# Microcontroller_Unit.net
KiCad netlist of a schematic drawn in Altium Designer
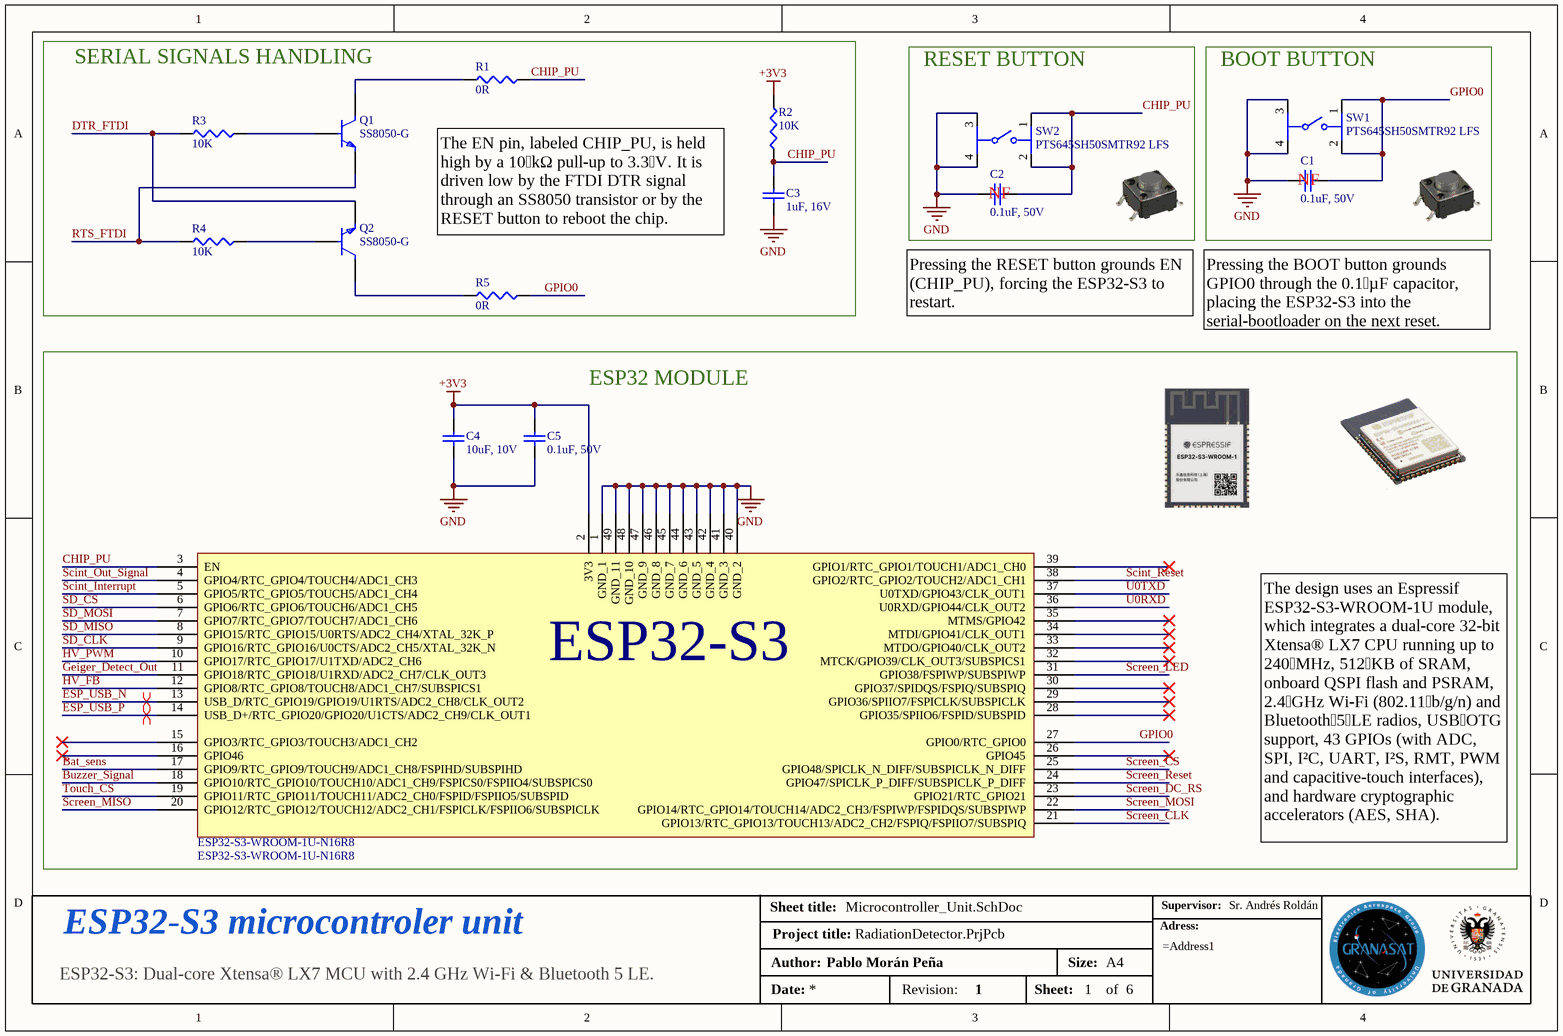
[diagram p0: Microcontroller_Unit.SchDoc]

(export (version "E")
  (design (tool "Eeschema 10.0.6"))
  (components
    (comp (ref "C1")
      (value "0.1uF, 50V")
      (footprint "CAP 0402_1005")
      (description "CAP CER 0.1UF 50V X7R 0402")
      (fields
        (field (name "MANUFACTURER") "Samsung")
        (field (name "MANUFACTURER PART NUMBER") "CL05B104KB5NNNC")
      )
      (libsource (lib "Schlib") (part "CL05B104KB5NNNC"))
    )
    (comp (ref "C2")
      (value "0.1uF, 50V")
      (footprint "CAP 0402_1005")
      (description "CAP CER 0.1UF 50V X7R 0402")
      (fields
        (field (name "MANUFACTURER") "Samsung")
        (field (name "MANUFACTURER PART NUMBER") "CL05B104KB5NNNC")
      )
      (libsource (lib "Schlib") (part "CL05B104KB5NNNC"))
    )
    (comp (ref "C3")
      (value "1uF, 16V")
      (footprint "CAP 0402_1005")
      (description "CAP CER 1UF 16V X5R 0402")
      (fields
        (field (name "MANUFACTURER") "Samsung Electro-Mechanics")
        (field (name "MANUFACTURER PART NUMBER") "CL05A105KO5NNNC")
      )
      (libsource (lib "Schlib") (part "CL05A105KO5NNNC"))
    )
    (comp (ref "C4")
      (value "10uF, 10V")
      (footprint "CAP 0402_1005")
      (description "CAP CER 10UF 10V X5R 0402")
      (fields
        (field (name "MANUFACTURER") "Samsung Electro-Mechanics")
        (field (name "MANUFACTURER PART NUMBER") "CL05A106MP8NUB8")
      )
      (libsource (lib "Schlib") (part "CL05A106MP8NUB8"))
    )
    (comp (ref "C5")
      (value "0.1uF, 50V")
      (footprint "CAP 0402_1005")
      (description "CAP CER 0.1UF 50V X7R 0402")
      (fields
        (field (name "MANUFACTURER") "Samsung")
        (field (name "MANUFACTURER PART NUMBER") "CL05B104KB5NNNC")
      )
      (libsource (lib "Schlib") (part "CL05B104KB5NNNC"))
    )
    (comp (ref "ESP32-S3-WROOM-1U-N16R8")
      (value "ESP32-S3-WROOM-1U-N16R8")
      (footprint "ESP32S3WROOM1N8R2")
      (description "SMD Module, ESP32-S3R8 With 8 mb")
      (fields (field (name "MANUFACTURER") "Espressif Systems") (field (name "LCSC PART NUMBER") "C2913202"))
      (libsource (lib "Schlib") (part "ESP32-S3-WROOM-1-N16R8"))
    )
    (comp (ref "Q1")
      (value "SS8050-G")
      (footprint "FP-SS8050-G-IPC_B")
      (description "Transistores - Bipolar (BJT) - Simple NPN 25 V 1.5 A 100MHz 300 mW Montaje en superficie SOT-23-3")
      (fields (field (name "MANUFACTURER") "Comchip") (field (name "LCSC PART NUMBER") "C164886"))
      (libsource (lib "Schlib") (part "SS8050-G"))
    )
    (comp (ref "Q2")
      (value "SS8050-G")
      (footprint "FP-SS8050-G-IPC_B")
      (description "Transistores - Bipolar (BJT) - Simple NPN 25 V 1.5 A 100MHz 300 mW Montaje en superficie SOT-23-3")
      (fields (field (name "MANUFACTURER") "Comchip") (field (name "LCSC PART NUMBER") "C164886"))
      (libsource (lib "Schlib") (part "SS8050-G"))
    )
    (comp (ref "R1")
      (value "0R")
      (footprint "RESC1005X37N")
      (description "RES 0 OHM JUMPER 1/16W 0402")
      (fields
        (field (name "MANUFACTURER") "Yageo")
        (field (name "MANUFACTURER PART NUMBER") "RC0402JR-070RL")
      )
      (libsource (lib "Schlib") (part "RC0402JR-070RL"))
    )
    (comp (ref "R2")
      (value "10K")
      (footprint "RESC1005X37N")
      (description "RES SMD 10K OHM 1% 1/16W 0402")
      (fields
        (field (name "MANUFACTURER") "Yageo")
        (field (name "MANUFACTURER PART NUMBER") "AC0402FR-0710KL")
      )
      (libsource (lib "Schlib") (part "AC0402FR-0710KL"))
    )
    (comp (ref "R3")
      (value "10K")
      (footprint "RESC1005X37N")
      (description "RES SMD 10K OHM 1% 1/16W 0402")
      (fields
        (field (name "MANUFACTURER") "Yageo")
        (field (name "MANUFACTURER PART NUMBER") "AC0402FR-0710KL")
      )
      (libsource (lib "Schlib") (part "AC0402FR-0710KL"))
    )
    (comp (ref "R4")
      (value "10K")
      (footprint "RESC1005X37N")
      (description "RES SMD 10K OHM 1% 1/16W 0402")
      (fields
        (field (name "MANUFACTURER") "Yageo")
        (field (name "MANUFACTURER PART NUMBER") "AC0402FR-0710KL")
      )
      (libsource (lib "Schlib") (part "AC0402FR-0710KL"))
    )
    (comp (ref "R5")
      (value "0R")
      (footprint "RESC1005X37N")
      (description "RES 0 OHM JUMPER 1/16W 0402")
      (fields
        (field (name "MANUFACTURER") "Yageo")
        (field (name "MANUFACTURER PART NUMBER") "RC0402JR-070RL")
      )
      (libsource (lib "Schlib") (part "RC0402JR-070RL"))
    )
    (comp (ref "SW1")
      (value "PTS645SH50SMTR92 LFS")
      (footprint "FP-PTS645SH50SMTR92LFS-MFG")
      (description "SWITCH TACTILE SPST-NO 0.05A 12V")
      (fields
        (field (name "MANUFACTURER") "ITT C&K")
        (field (name "MANUFACTURER PART NUMBER") "PTS645SH50SMTR92LFS")
      )
      (libsource (lib "Schlib") (part "PTS645SH50SMTR92LFS"))
    )
    (comp (ref "SW2")
      (value "PTS645SH50SMTR92 LFS")
      (footprint "FP-PTS645SH50SMTR92LFS-MFG")
      (description "SWITCH TACTILE SPST-NO 0.05A 12V")
      (fields
        (field (name "MANUFACTURER") "ITT C&K")
        (field (name "MANUFACTURER PART NUMBER") "PTS645SH50SMTR92LFS")
      )
      (libsource (lib "Schlib") (part "PTS645SH50SMTR92LFS"))
    )
  )
  (nets
    (net (code "1") (name "+3V3") (class "Default")
      (node (ref "C4") (pin "2") (pinfunction "2_2") (pintype "passive"))
      (node (ref "C5") (pin "2") (pinfunction "2_2") (pintype "passive"))
      (node (ref "ESP32-S3-WROOM-1U-N16R8") (pin "2") (pinfunction "3V3_2") (pintype "passive"))
      (node (ref "R2") (pin "2") (pinfunction "2_2") (pintype "passive"))
    )
    (net (code "2") (name "/Bat_sens") (class "Default")
      (node (ref "ESP32-S3-WROOM-1U-N16R8") (pin "17") (pinfunction "GPIO9/RTC_GPIO9/TOUCH9/ADC1_CH8/FSPIHD/SUBSPIHD_17") (pintype "passive"))
    )
    (net (code "3") (name "/Buzzer_Signal") (class "Default")
      (node (ref "ESP32-S3-WROOM-1U-N16R8") (pin "18") (pinfunction "GPIO10/RTC_GPIO10/TOUCH10/ADC1_CH9/FSPICS0/FSPIIO4/SUBSPICS0_18") (pintype "passive"))
    )
    (net (code "4") (name "/CHIP_PU") (class "Default")
      (node (ref "C2") (pin "2") (pinfunction "2_2") (pintype "passive"))
      (node (ref "C3") (pin "2") (pinfunction "2_2") (pintype "passive"))
      (node (ref "ESP32-S3-WROOM-1U-N16R8") (pin "3") (pinfunction "EN_3") (pintype "passive"))
      (node (ref "R1") (pin "2") (pinfunction "2_2") (pintype "passive"))
      (node (ref "R2") (pin "1") (pinfunction "1_1") (pintype "passive"))
      (node (ref "SW2") (pin "1") (pinfunction "1_1") (pintype "passive"))
      (node (ref "SW2") (pin "2") (pinfunction "2_2") (pintype "passive"))
    )
    (net (code "5") (name "/DTR_FTDI") (class "Default")
      (node (ref "Q2") (pin "2") (pinfunction "E_2") (pintype "passive"))
      (node (ref "R3") (pin "1") (pinfunction "1_1") (pintype "passive"))
    )
    (net (code "6") (name "/ESP_USB_N") (class "Default")
      (node (ref "ESP32-S3-WROOM-1U-N16R8") (pin "13") (pinfunction "USB_D/RTC_GPIO19/GPIO19/U1RTS/ADC2_CH8/CLK_OUT2_13") (pintype "passive"))
    )
    (net (code "7") (name "/ESP_USB_P") (class "Default")
      (node (ref "ESP32-S3-WROOM-1U-N16R8") (pin "14") (pinfunction "USB_D+/RTC_GPIO20/GPIO20/U1CTS/ADC2_CH9/CLK_OUT1_14") (pintype "passive"))
    )
    (net (code "8") (name "/GPIO0") (class "Default")
      (node (ref "C1") (pin "2") (pinfunction "2_2") (pintype "passive"))
      (node (ref "ESP32-S3-WROOM-1U-N16R8") (pin "27") (pinfunction "GPIO0/RTC_GPIO0_27") (pintype "passive"))
      (node (ref "R5") (pin "2") (pinfunction "2_2") (pintype "passive"))
      (node (ref "SW1") (pin "1") (pinfunction "1_1") (pintype "passive"))
      (node (ref "SW1") (pin "2") (pinfunction "2_2") (pintype "passive"))
    )
    (net (code "9") (name "/Geiger_Detect_Out") (class "Default")
      (node (ref "ESP32-S3-WROOM-1U-N16R8") (pin "11") (pinfunction "GPIO18/RTC_GPIO18/U1RXD/ADC2_CH7/CLK_OUT3_11") (pintype "passive"))
    )
    (net (code "10") (name "/HV_FB") (class "Default")
      (node (ref "ESP32-S3-WROOM-1U-N16R8") (pin "12") (pinfunction "GPIO8/RTC_GPIO8/TOUCH8/ADC1_CH7/SUBSPICS1_12") (pintype "passive"))
    )
    (net (code "11") (name "/HV_PWM") (class "Default")
      (node (ref "ESP32-S3-WROOM-1U-N16R8") (pin "10") (pinfunction "GPIO17/RTC_GPIO17/U1TXD/ADC2_CH6_10") (pintype "passive"))
    )
    (net (code "12") (name "/RTS_FTDI") (class "Default")
      (node (ref "Q1") (pin "2") (pinfunction "E_2") (pintype "passive"))
      (node (ref "R4") (pin "1") (pinfunction "1_1") (pintype "passive"))
    )
    (net (code "13") (name "/SD_CLK") (class "Default")
      (node (ref "ESP32-S3-WROOM-1U-N16R8") (pin "9") (pinfunction "GPIO16/RTC_GPIO16/U0CTS/ADC2_CH5/XTAL_32K_N_9") (pintype "passive"))
    )
    (net (code "14") (name "/SD_CS") (class "Default")
      (node (ref "ESP32-S3-WROOM-1U-N16R8") (pin "6") (pinfunction "GPIO6/RTC_GPIO6/TOUCH6/ADC1_CH5_6") (pintype "passive"))
    )
    (net (code "15") (name "/SD_MISO") (class "Default")
      (node (ref "ESP32-S3-WROOM-1U-N16R8") (pin "8") (pinfunction "GPIO15/RTC_GPIO15/U0RTS/ADC2_CH4/XTAL_32K_P_8") (pintype "passive"))
    )
    (net (code "16") (name "/SD_MOSI") (class "Default")
      (node (ref "ESP32-S3-WROOM-1U-N16R8") (pin "7") (pinfunction "GPIO7/RTC_GPIO7/TOUCH7/ADC1_CH6_7") (pintype "passive"))
    )
    (net (code "17") (name "/Scint_Interrupt") (class "Default")
      (node (ref "ESP32-S3-WROOM-1U-N16R8") (pin "5") (pinfunction "GPIO5/RTC_GPIO5/TOUCH5/ADC1_CH4_5") (pintype "passive"))
    )
    (net (code "18") (name "/Scint_Out_Signal") (class "Default")
      (node (ref "ESP32-S3-WROOM-1U-N16R8") (pin "4") (pinfunction "GPIO4/RTC_GPIO4/TOUCH4/ADC1_CH3_4") (pintype "passive"))
    )
    (net (code "19") (name "/Scint_Reset") (class "Default")
      (node (ref "ESP32-S3-WROOM-1U-N16R8") (pin "38") (pinfunction "GPIO2/RTC_GPIO2/TOUCH2/ADC1_CH1_38") (pintype "passive"))
    )
    (net (code "20") (name "/Screen_CLK") (class "Default")
      (node (ref "ESP32-S3-WROOM-1U-N16R8") (pin "21") (pinfunction "GPIO13/RTC_GPIO13/TOUCH13/ADC2_CH2/FSPIQ/FSPIIO7/SUBSPIQ_21") (pintype "passive"))
    )
    (net (code "21") (name "/Screen_CS") (class "Default")
      (node (ref "ESP32-S3-WROOM-1U-N16R8") (pin "25") (pinfunction "GPIO48/SPICLK_N_DIFF/SUBSPICLK_N_DIFF_25") (pintype "passive"))
    )
    (net (code "22") (name "/Screen_DC_RS") (class "Default")
      (node (ref "ESP32-S3-WROOM-1U-N16R8") (pin "23") (pinfunction "GPIO21/RTC_GPIO21_23") (pintype "passive"))
    )
    (net (code "23") (name "/Screen_LED") (class "Default")
      (node (ref "ESP32-S3-WROOM-1U-N16R8") (pin "31") (pinfunction "GPIO38/FSPIWP/SUBSPIWP_31") (pintype "passive"))
    )
    (net (code "24") (name "/Screen_MISO") (class "Default")
      (node (ref "ESP32-S3-WROOM-1U-N16R8") (pin "20") (pinfunction "GPIO12/RTC_GPIO12/TOUCH12/ADC2_CH1/FSPICLK/FSPIIO6/SUBSPICLK_20") (pintype "passive"))
    )
    (net (code "25") (name "/Screen_MOSI") (class "Default")
      (node (ref "ESP32-S3-WROOM-1U-N16R8") (pin "22") (pinfunction "GPIO14/RTC_GPIO14/TOUCH14/ADC2_CH3/FSPIWP/FSPIDQS/SUBSPIWP_22") (pintype "passive"))
    )
    (net (code "26") (name "/Screen_Reset") (class "Default")
      (node (ref "ESP32-S3-WROOM-1U-N16R8") (pin "24") (pinfunction "GPIO47/SPICLK_P_DIFF/SUBSPICLK_P_DIFF_24") (pintype "passive"))
    )
    (net (code "27") (name "/Touch_CS") (class "Default")
      (node (ref "ESP32-S3-WROOM-1U-N16R8") (pin "19") (pinfunction "GPIO11/RTC_GPIO11/TOUCH11/ADC2_CH0/FSPID/FSPIIO5/SUBSPID_19") (pintype "passive"))
    )
    (net (code "28") (name "/U0RXD") (class "Default")
      (node (ref "ESP32-S3-WROOM-1U-N16R8") (pin "36") (pinfunction "U0RXD/GPIO44/CLK_OUT2_36") (pintype "passive"))
    )
    (net (code "29") (name "/U0TXD") (class "Default")
      (node (ref "ESP32-S3-WROOM-1U-N16R8") (pin "37") (pinfunction "U0TXD/GPIO43/CLK_OUT1_37") (pintype "passive"))
    )
    (net (code "30") (name "GND") (class "Default")
      (node (ref "C1") (pin "1") (pinfunction "1_1") (pintype "passive"))
      (node (ref "C2") (pin "1") (pinfunction "1_1") (pintype "passive"))
      (node (ref "C3") (pin "1") (pinfunction "1_1") (pintype "passive"))
      (node (ref "C4") (pin "1") (pinfunction "1_1") (pintype "passive"))
      (node (ref "C5") (pin "1") (pinfunction "1_1") (pintype "passive"))
      (node (ref "ESP32-S3-WROOM-1U-N16R8") (pin "1") (pinfunction "GND_1_1") (pintype "passive"))
      (node (ref "ESP32-S3-WROOM-1U-N16R8") (pin "40") (pinfunction "GND_2_40") (pintype "passive"))
      (node (ref "ESP32-S3-WROOM-1U-N16R8") (pin "41") (pinfunction "GND_3_41") (pintype "passive"))
      (node (ref "ESP32-S3-WROOM-1U-N16R8") (pin "42") (pinfunction "GND_4_42") (pintype "passive"))
      (node (ref "ESP32-S3-WROOM-1U-N16R8") (pin "43") (pinfunction "GND_5_43") (pintype "passive"))
      (node (ref "ESP32-S3-WROOM-1U-N16R8") (pin "44") (pinfunction "GND_6_44") (pintype "passive"))
      (node (ref "ESP32-S3-WROOM-1U-N16R8") (pin "45") (pinfunction "GND_7_45") (pintype "passive"))
      (node (ref "ESP32-S3-WROOM-1U-N16R8") (pin "46") (pinfunction "GND_8_46") (pintype "passive"))
      (node (ref "ESP32-S3-WROOM-1U-N16R8") (pin "47") (pinfunction "GND_9_47") (pintype "passive"))
      (node (ref "ESP32-S3-WROOM-1U-N16R8") (pin "48") (pinfunction "GND_10_48") (pintype "passive"))
      (node (ref "ESP32-S3-WROOM-1U-N16R8") (pin "49") (pinfunction "GND_11_49") (pintype "passive"))
      (node (ref "SW1") (pin "3") (pinfunction "3_3") (pintype "passive"))
      (node (ref "SW1") (pin "4") (pinfunction "4_4") (pintype "passive"))
      (node (ref "SW2") (pin "3") (pinfunction "3_3") (pintype "passive"))
      (node (ref "SW2") (pin "4") (pinfunction "4_4") (pintype "passive"))
    )
    (net (code "31") (name "Net-(Q1-B)") (class "Default")
      (node (ref "Q1") (pin "1") (pinfunction "B_1") (pintype "passive"))
      (node (ref "R3") (pin "2") (pinfunction "2_2") (pintype "passive"))
    )
    (net (code "32") (name "Net-(Q1-C)") (class "Default")
      (node (ref "Q1") (pin "3") (pinfunction "C_3") (pintype "passive"))
      (node (ref "R1") (pin "1") (pinfunction "1_1") (pintype "passive"))
    )
    (net (code "33") (name "Net-(Q2-B)") (class "Default")
      (node (ref "Q2") (pin "1") (pinfunction "B_1") (pintype "passive"))
      (node (ref "R4") (pin "2") (pinfunction "2_2") (pintype "passive"))
    )
    (net (code "34") (name "Net-(Q2-C)") (class "Default")
      (node (ref "Q2") (pin "3") (pinfunction "C_3") (pintype "passive"))
      (node (ref "R5") (pin "1") (pinfunction "1_1") (pintype "passive"))
    )
    (net (code "35") (name "unconnected-(ESP32-S3-WROOM-1U-N16R8-GPIO1{slash}RTC_GPIO1{slash}TOUCH1{slash}ADC1_CH0-Pad39)") (class "Default")
      (node (ref "ESP32-S3-WROOM-1U-N16R8") (pin "39") (pinfunction "GPIO1/RTC_GPIO1/TOUCH1/ADC1_CH0_39") (pintype "passive+no_connect"))
    )
    (net (code "36") (name "unconnected-(ESP32-S3-WROOM-1U-N16R8-GPIO3{slash}RTC_GPIO3{slash}TOUCH3{slash}ADC1_CH2-Pad15)") (class "Default")
      (node (ref "ESP32-S3-WROOM-1U-N16R8") (pin "15") (pinfunction "GPIO3/RTC_GPIO3/TOUCH3/ADC1_CH2_15") (pintype "passive+no_connect"))
    )
    (net (code "37") (name "unconnected-(ESP32-S3-WROOM-1U-N16R8-GPIO35{slash}SPIIO6{slash}FSPID{slash}SUBSPID-Pad28)") (class "Default")
      (node (ref "ESP32-S3-WROOM-1U-N16R8") (pin "28") (pinfunction "GPIO35/SPIIO6/FSPID/SUBSPID_28") (pintype "passive+no_connect"))
    )
    (net (code "38") (name "unconnected-(ESP32-S3-WROOM-1U-N16R8-GPIO36{slash}SPIIO7{slash}FSPICLK{slash}SUBSPICLK-Pad29)") (class "Default")
      (node (ref "ESP32-S3-WROOM-1U-N16R8") (pin "29") (pinfunction "GPIO36/SPIIO7/FSPICLK/SUBSPICLK_29") (pintype "passive+no_connect"))
    )
    (net (code "39") (name "unconnected-(ESP32-S3-WROOM-1U-N16R8-GPIO37{slash}SPIDQS{slash}FSPIQ{slash}SUBSPIQ-Pad30)") (class "Default")
      (node (ref "ESP32-S3-WROOM-1U-N16R8") (pin "30") (pinfunction "GPIO37/SPIDQS/FSPIQ/SUBSPIQ_30") (pintype "passive+no_connect"))
    )
    (net (code "40") (name "unconnected-(ESP32-S3-WROOM-1U-N16R8-GPIO45-Pad26)") (class "Default")
      (node (ref "ESP32-S3-WROOM-1U-N16R8") (pin "26") (pinfunction "GPIO45_26") (pintype "passive+no_connect"))
    )
    (net (code "41") (name "unconnected-(ESP32-S3-WROOM-1U-N16R8-GPIO46-Pad16)") (class "Default")
      (node (ref "ESP32-S3-WROOM-1U-N16R8") (pin "16") (pinfunction "GPIO46_16") (pintype "passive+no_connect"))
    )
    (net (code "42") (name "unconnected-(ESP32-S3-WROOM-1U-N16R8-MTCK{slash}GPIO39{slash}CLK_OUT3{slash}SUBSPICS1-Pad32)") (class "Default")
      (node (ref "ESP32-S3-WROOM-1U-N16R8") (pin "32") (pinfunction "MTCK/GPIO39/CLK_OUT3/SUBSPICS1_32") (pintype "passive+no_connect"))
    )
    (net (code "43") (name "unconnected-(ESP32-S3-WROOM-1U-N16R8-MTDI{slash}GPIO41{slash}CLK_OUT1-Pad34)") (class "Default")
      (node (ref "ESP32-S3-WROOM-1U-N16R8") (pin "34") (pinfunction "MTDI/GPIO41/CLK_OUT1_34") (pintype "passive+no_connect"))
    )
    (net (code "44") (name "unconnected-(ESP32-S3-WROOM-1U-N16R8-MTDO{slash}GPIO40{slash}CLK_OUT2-Pad33)") (class "Default")
      (node (ref "ESP32-S3-WROOM-1U-N16R8") (pin "33") (pinfunction "MTDO/GPIO40/CLK_OUT2_33") (pintype "passive+no_connect"))
    )
    (net (code "45") (name "unconnected-(ESP32-S3-WROOM-1U-N16R8-MTMS{slash}GPIO42-Pad35)") (class "Default")
      (node (ref "ESP32-S3-WROOM-1U-N16R8") (pin "35") (pinfunction "MTMS/GPIO42_35") (pintype "passive+no_connect"))
    )
  )
)
